# ESP01_Breakout.net
KiCad netlist of a schematic drawn in EAGLE
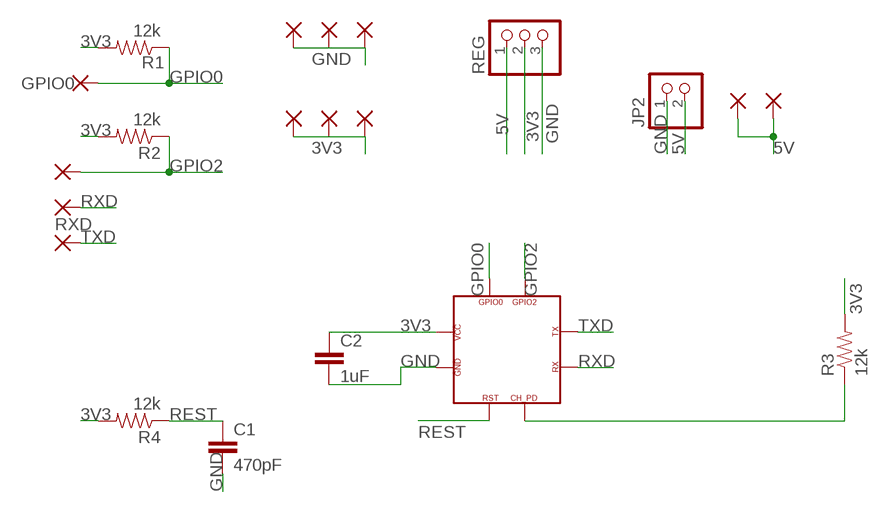
[diagram p0: schematic, sheet 1]

(export (version "E")
  (design (tool "Eeschema 10.0.6"))
  (components
    (comp (ref "C1")
      (value "470pF")
      (footprint "eagle-import:CAP-PTH-SMALLEZ")
      (libsource (lib "eagle-import") (part "CAPEZ"))
    )
    (comp (ref "C2")
      (value "1uF")
      (footprint "eagle-import:CAP-PTH-SMALLEZ")
      (libsource (lib "eagle-import") (part "CAPEZ"))
    )
    (comp (ref "GPIO0")
      (value "1,6/0,9")
      (footprint "eagle-import:1,6_0,9")
      (libsource (lib "eagle-import") (part "1,6/0,9"))
    )
    (comp (ref "GPIO1")
      (value "1,6/0,9")
      (footprint "eagle-import:1,6_0,9")
      (libsource (lib "eagle-import") (part "1,6/0,9"))
    )
    (comp (ref "GPIO2")
      (value "1,6/0,9")
      (footprint "eagle-import:1,6_0,9")
      (libsource (lib "eagle-import") (part "1,6/0,9"))
    )
    (comp (ref "GPIO3")
      (value "1,6/0,9")
      (footprint "eagle-import:1,6_0,9")
      (libsource (lib "eagle-import") (part "1,6/0,9"))
    )
    (comp (ref "GPIO4")
      (value "1,6/0,9")
      (footprint "eagle-import:1,6_0,9")
      (libsource (lib "eagle-import") (part "1,6/0,9"))
    )
    (comp (ref "GPIO5")
      (value "1,6/0,9")
      (footprint "eagle-import:1,6_0,9")
      (libsource (lib "eagle-import") (part "1,6/0,9"))
    )
    (comp (ref "GPIO6")
      (value "1,6/0,9")
      (footprint "eagle-import:1,6_0,9")
      (libsource (lib "eagle-import") (part "1,6/0,9"))
    )
    (comp (ref "GPIO7")
      (value "1,6/0,9")
      (footprint "eagle-import:1,6_0,9")
      (libsource (lib "eagle-import") (part "1,6/0,9"))
    )
    (comp (ref "GPIO8")
      (value "1,6/0,9")
      (footprint "eagle-import:1,6_0,9")
      (libsource (lib "eagle-import") (part "1,6/0,9"))
    )
    (comp (ref "GPIO9")
      (value "1,6/0,9")
      (footprint "eagle-import:1,6_0,9")
      (libsource (lib "eagle-import") (part "1,6/0,9"))
    )
    (comp (ref "GPIO10")
      (value "1,6/0,9")
      (footprint "eagle-import:1,6_0,9")
      (libsource (lib "eagle-import") (part "1,6/0,9"))
    )
    (comp (ref "JP2")
      (value "PINHD-1X2/90")
      (footprint "eagle-import:1X02_90")
      (libsource (lib "eagle-import") (part "PINHD-1X2/90"))
    )
    (comp (ref "R1")
      (value "12k")
      (footprint "eagle-import:AXIAL-0.4")
      (libsource (lib "eagle-import") (part "RESISTORPTH-1/4W"))
    )
    (comp (ref "R2")
      (value "12k")
      (footprint "eagle-import:AXIAL-0.4")
      (libsource (lib "eagle-import") (part "RESISTORPTH-1/4W"))
    )
    (comp (ref "R3")
      (value "12k")
      (footprint "eagle-import:AXIAL-0.4")
      (libsource (lib "eagle-import") (part "RESISTORPTH-1/4W"))
    )
    (comp (ref "R4")
      (value "12k")
      (footprint "eagle-import:AXIAL-0.4")
      (libsource (lib "eagle-import") (part "RESISTORPTH-1/4W"))
    )
    (comp (ref "REG")
      (value "PINHD-1X3")
      (footprint "eagle-import:1X03")
      (libsource (lib "eagle-import") (part "PINHD-1X3"))
    )
    (comp (ref "RXD")
      (value "RXD")
      (footprint "eagle-import:1,6_0,9")
      (libsource (lib "eagle-import") (part "1,6/0,9"))
    )
    (comp (ref "U$2")
      (value "ESP-01")
      (footprint "eagle-import:ESP-01")
      (libsource (lib "eagle-import") (part "ESP-01"))
    )
  )
  (nets
    (net (code "1") (name "/3V3") (class "Default")
      (node (ref "C2") (pin "1") (pinfunction "1_1") (pintype "passive"))
      (node (ref "GPIO6") (pin "1") (pinfunction "P_1") (pintype "passive"))
      (node (ref "GPIO7") (pin "1") (pinfunction "P_1") (pintype "passive"))
      (node (ref "GPIO8") (pin "1") (pinfunction "P_1") (pintype "passive"))
      (node (ref "R1") (pin "P$2") (pinfunction "2_P$2") (pintype "passive"))
      (node (ref "R2") (pin "P$2") (pinfunction "2_P$2") (pintype "passive"))
      (node (ref "R3") (pin "P$2") (pinfunction "2_P$2") (pintype "passive"))
      (node (ref "R4") (pin "P$2") (pinfunction "2_P$2") (pintype "passive"))
      (node (ref "REG") (pin "2") (pinfunction "2_2") (pintype "passive"))
      (node (ref "U$2") (pin "VCC") (pinfunction "VCC_VCC") (pintype "bidirectional"))
    )
    (net (code "2") (name "/5V") (class "Default")
      (node (ref "GPIO10") (pin "1") (pinfunction "P_1") (pintype "passive"))
      (node (ref "GPIO9") (pin "1") (pinfunction "P_1") (pintype "passive"))
      (node (ref "JP2") (pin "2") (pinfunction "2_2") (pintype "passive"))
      (node (ref "REG") (pin "1") (pinfunction "1_1") (pintype "passive"))
    )
    (net (code "3") (name "/GND") (class "Default")
      (node (ref "C1") (pin "2") (pinfunction "2_2") (pintype "passive"))
      (node (ref "C2") (pin "2") (pinfunction "2_2") (pintype "passive"))
      (node (ref "GPIO1") (pin "1") (pinfunction "P_1") (pintype "passive"))
      (node (ref "GPIO4") (pin "1") (pinfunction "P_1") (pintype "passive"))
      (node (ref "GPIO5") (pin "1") (pinfunction "P_1") (pintype "passive"))
      (node (ref "JP2") (pin "1") (pinfunction "1_1") (pintype "passive"))
      (node (ref "REG") (pin "3") (pinfunction "3_3") (pintype "passive"))
      (node (ref "U$2") (pin "GND") (pinfunction "GND_GND") (pintype "bidirectional"))
    )
    (net (code "4") (name "/GPIO0") (class "Default")
      (node (ref "GPIO0") (pin "1") (pinfunction "P_1") (pintype "passive"))
      (node (ref "R1") (pin "P$1") (pinfunction "1_P$1") (pintype "passive"))
      (node (ref "U$2") (pin "GPIO0") (pinfunction "GPIO0_GPIO0") (pintype "bidirectional"))
    )
    (net (code "5") (name "/GPIO2") (class "Default")
      (node (ref "GPIO2") (pin "1") (pinfunction "P_1") (pintype "passive"))
      (node (ref "R2") (pin "P$1") (pinfunction "1_P$1") (pintype "passive"))
      (node (ref "U$2") (pin "GPIO2") (pinfunction "GPIO2_GPIO2") (pintype "bidirectional"))
    )
    (net (code "6") (name "/REST") (class "Default")
      (node (ref "C1") (pin "1") (pinfunction "1_1") (pintype "passive"))
      (node (ref "R4") (pin "P$1") (pinfunction "1_P$1") (pintype "passive"))
      (node (ref "U$2") (pin "RST") (pinfunction "RST_RST") (pintype "bidirectional"))
    )
    (net (code "7") (name "/RXD") (class "Default")
      (node (ref "RXD") (pin "1") (pinfunction "P_1") (pintype "passive"))
      (node (ref "U$2") (pin "RXD") (pinfunction "RX_RXD") (pintype "bidirectional"))
    )
    (net (code "8") (name "/TXD") (class "Default")
      (node (ref "GPIO3") (pin "1") (pinfunction "P_1") (pintype "passive"))
      (node (ref "U$2") (pin "TXD") (pinfunction "TX_TXD") (pintype "bidirectional"))
    )
    (net (code "9") (name "Net-(R3-1)") (class "Default")
      (node (ref "R3") (pin "P$1") (pinfunction "1_P$1") (pintype "passive"))
      (node (ref "U$2") (pin "CH_PD") (pinfunction "CP_PD_CH_PD") (pintype "bidirectional"))
    )
  )
)
